# EE209_Sch_Team08.net
KiCad netlist of a schematic drawn in Altium Designer
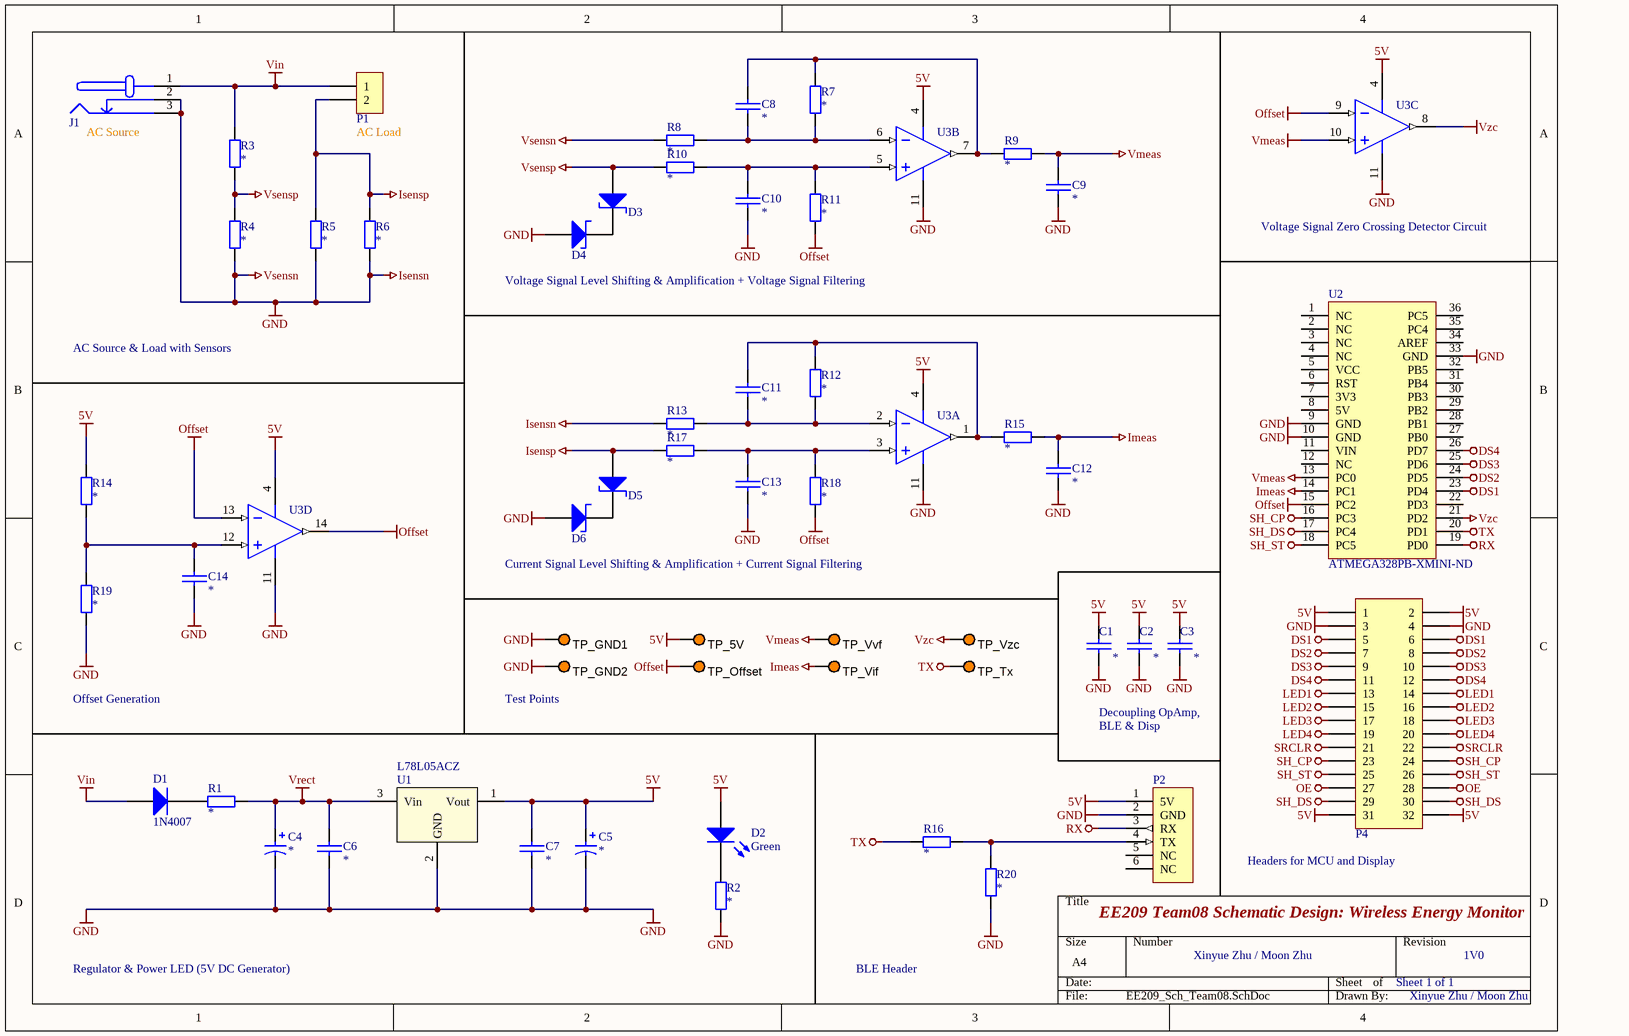
[diagram p0: EE209_Sch_Team08.SchDoc]

(export (version "E")
  (design (tool "Eeschema 10.0.6"))
  (components
    (comp (ref "C1")
      (value "*")
      (footprint "CCAP-5P0")
      (description "TH ceramic capacitor with 5mm pitch")
      (libsource (lib "EE209_Library") (part "CerCap_TH_5P0"))
    )
    (comp (ref "C2")
      (value "*")
      (footprint "CCAP-5P0")
      (description "TH ceramic capacitor with 5mm pitch")
      (libsource (lib "EE209_Library") (part "CerCap_TH_5P0"))
    )
    (comp (ref "C3")
      (value "*")
      (footprint "CCAP-5P0")
      (description "TH ceramic capacitor with 5mm pitch")
      (libsource (lib "EE209_Library") (part "CerCap_TH_5P0"))
    )
    (comp (ref "C4")
      (value "*")
      (footprint "CAP-RAD-2.5mm Pitch")
      (description "Electrolytic capacitor with radial package, 2mm pitch and 5.2mm diameter")
      (fields (field (name "PUBLISHER") "Altium Limited"))
      (libsource (lib "EE209_Library") (part "ElecCap_TH_2P0"))
    )
    (comp (ref "C5")
      (value "*")
      (footprint "CAP-RAD-2.5mm Pitch")
      (description "Electrolytic capacitor with radial package, 2mm pitch and 5.2mm diameter")
      (fields (field (name "PUBLISHER") "Altium Limited"))
      (libsource (lib "EE209_Library") (part "ElecCap_TH_2P0"))
    )
    (comp (ref "C6")
      (value "*")
      (footprint "CCAP-5P0")
      (description "TH ceramic capacitor with 5mm pitch")
      (libsource (lib "EE209_Library") (part "CerCap_TH_5P0"))
    )
    (comp (ref "C7")
      (value "*")
      (footprint "CCAP-5P0")
      (description "TH ceramic capacitor with 5mm pitch")
      (libsource (lib "EE209_Library") (part "CerCap_TH_5P0"))
    )
    (comp (ref "C8")
      (value "*")
      (footprint "CCAP-5P0")
      (description "TH ceramic capacitor with 5mm pitch")
      (libsource (lib "EE209_Library") (part "CerCap_TH_5P0"))
    )
    (comp (ref "C9")
      (value "*")
      (footprint "CCAP-5P0")
      (description "TH ceramic capacitor with 5mm pitch")
      (libsource (lib "EE209_Library") (part "CerCap_TH_5P0"))
    )
    (comp (ref "C10")
      (value "*")
      (footprint "CCAP-5P0")
      (description "TH ceramic capacitor with 5mm pitch")
      (libsource (lib "EE209_Library") (part "CerCap_TH_5P0"))
    )
    (comp (ref "C11")
      (value "*")
      (footprint "CCAP-5P0")
      (description "TH ceramic capacitor with 5mm pitch")
      (libsource (lib "EE209_Library") (part "CerCap_TH_5P0"))
    )
    (comp (ref "C12")
      (value "*")
      (footprint "CCAP-5P0")
      (description "TH ceramic capacitor with 5mm pitch")
      (libsource (lib "EE209_Library") (part "CerCap_TH_5P0"))
    )
    (comp (ref "C13")
      (value "*")
      (footprint "CCAP-5P0")
      (description "TH ceramic capacitor with 5mm pitch")
      (libsource (lib "EE209_Library") (part "CerCap_TH_5P0"))
    )
    (comp (ref "C14")
      (value "*")
      (footprint "CCAP-5P0")
      (description "TH ceramic capacitor with 5mm pitch")
      (libsource (lib "EE209_Library") (part "CerCap_TH_5P0"))
    )
    (comp (ref "D1")
      (value "1N4007")
      (footprint "1N4007-MFG")
      (description "1N4007 1000V standard axial diode")
      (libsource (lib "EE209_Library") (part "1N4007_TH_4AX0"))
    )
    (comp (ref "D2")
      (value "Green")
      (footprint "LED")
      (description "Typical throughole GaAs LED with 2.54mm pitch")
      (fields (field (name "MANUFACTURER") "Generic Components") (field (name "PUBLISHER") "Altium Limited"))
      (libsource (lib "EE209_Library") (part "LED_TH_2P54"))
    )
    (comp (ref "D3")
      (value "BZX79-CXVX")
      (footprint "AXIAL-Zener-0.4")
      (description "Axial zener diode BZX79 series")
      (fields
        (field (name "MANUFACTURER") "Nexperia USA Inc.")
        (field (name "MANUFACTURER PART NUMBER") "BZX79-C4V7,143")
      )
      (libsource (lib "EE209_Library") (part "Zener_TH_4AX0"))
    )
    (comp (ref "D4")
      (value "BZX79-CXVX")
      (footprint "AXIAL-Zener-0.4")
      (description "Axial zener diode BZX79 series")
      (fields
        (field (name "MANUFACTURER") "Nexperia USA Inc.")
        (field (name "MANUFACTURER PART NUMBER") "BZX79-C4V7,143")
      )
      (libsource (lib "EE209_Library") (part "Zener_TH_4AX0"))
    )
    (comp (ref "D5")
      (value "BZX79-CXVX")
      (footprint "AXIAL-Zener-0.4")
      (description "Axial zener diode BZX79 series")
      (fields
        (field (name "MANUFACTURER") "Nexperia USA Inc.")
        (field (name "MANUFACTURER PART NUMBER") "BZX79-C4V7,143")
      )
      (libsource (lib "EE209_Library") (part "Zener_TH_4AX0"))
    )
    (comp (ref "D6")
      (value "BZX79-CXVX")
      (footprint "AXIAL-Zener-0.4")
      (description "Axial zener diode BZX79 series")
      (fields
        (field (name "MANUFACTURER") "Nexperia USA Inc.")
        (field (name "MANUFACTURER PART NUMBER") "BZX79-C4V7,143")
      )
      (libsource (lib "EE209_Library") (part "Zener_TH_4AX0"))
    )
    (comp (ref "J1")
      (value "DC barrel jack")
      (footprint "AC-Socket")
      (description "DC barrel jack connection to AC source")
      (libsource (lib "EE209_Library") (part "AC_Input"))
    )
    (comp (ref "P1")
      (value "Dual Banana Plugs")
      (footprint "Dual Banana Plug")
      (description "Dual banana plugs connection to the AC load")
      (fields (field (name "PUBLISHER") "Altium Limited"))
      (libsource (lib "EE209_Library") (part "AC_Output"))
    )
    (comp (ref "P2")
      (value "BLE Module Header")
      (footprint "HM10_HDR1X6")
      (description "2.54mm pitch 6-pin header for BLE module")
      (fields (field (name "PUBLISHER") "Altium Limited"))
      (libsource (lib "EE209_Library") (part "BLEModule_TH"))
    )
    (comp (ref "P4")
      (value "Display")
      (footprint "Display")
      (description "16-Pin Header Connecting Display")
      (libsource (lib "EE209_Library") (part "Display"))
    )
    (comp (ref "R1")
      (value "*")
      (footprint "AXIAL-0.4")
      (description "Through hole resistor")
      (fields (field (name "PUBLISHER") "Altium Limited"))
      (libsource (lib "") (part "Res_TH_0AX4_1"))
    )
    (comp (ref "R2")
      (value "*")
      (footprint "AXIAL-0.4")
      (description "Through hole resistor")
      (fields (field (name "PUBLISHER") "Altium Limited"))
      (libsource (lib "") (part "Res_TH_0AX4_2"))
    )
    (comp (ref "R3")
      (value "*")
      (footprint "AXIAL-0.4")
      (description "Through hole resistor")
      (fields (field (name "PUBLISHER") "Altium Limited"))
      (libsource (lib "") (part "Res_TH_0AX4_2"))
    )
    (comp (ref "R4")
      (value "*")
      (footprint "AXIAL-0.4")
      (description "Through hole resistor")
      (fields (field (name "PUBLISHER") "Altium Limited"))
      (libsource (lib "") (part "Res_TH_0AX4_2"))
    )
    (comp (ref "R5")
      (value "*")
      (footprint "AXIAL-0.4")
      (description "Through hole resistor")
      (fields (field (name "PUBLISHER") "Altium Limited"))
      (libsource (lib "") (part "Res_TH_0AX4_2"))
    )
    (comp (ref "R6")
      (value "*")
      (footprint "AXIAL-0.4")
      (description "Through hole resistor")
      (fields (field (name "PUBLISHER") "Altium Limited"))
      (libsource (lib "") (part "Res_TH_0AX4_2"))
    )
    (comp (ref "R7")
      (value "*")
      (footprint "AXIAL-0.4")
      (description "Through hole resistor")
      (fields (field (name "PUBLISHER") "Altium Limited"))
      (libsource (lib "") (part "Res_TH_0AX4_2"))
    )
    (comp (ref "R8")
      (value "*")
      (footprint "AXIAL-0.4")
      (description "Through hole resistor")
      (fields (field (name "PUBLISHER") "Altium Limited"))
      (libsource (lib "EE209_Library") (part "Res_TH_0AX4"))
    )
    (comp (ref "R9")
      (value "*")
      (footprint "AXIAL-0.4")
      (description "Through hole resistor")
      (fields (field (name "PUBLISHER") "Altium Limited"))
      (libsource (lib "EE209_Library") (part "Res_TH_0AX4"))
    )
    (comp (ref "R10")
      (value "*")
      (footprint "AXIAL-0.4")
      (description "Through hole resistor")
      (fields (field (name "PUBLISHER") "Altium Limited"))
      (libsource (lib "EE209_Library") (part "Res_TH_0AX4"))
    )
    (comp (ref "R11")
      (value "*")
      (footprint "AXIAL-0.4")
      (description "Through hole resistor")
      (fields (field (name "PUBLISHER") "Altium Limited"))
      (libsource (lib "") (part "Res_TH_0AX4_2"))
    )
    (comp (ref "R12")
      (value "*")
      (footprint "AXIAL-0.4")
      (description "Through hole resistor")
      (fields (field (name "PUBLISHER") "Altium Limited"))
      (libsource (lib "") (part "Res_TH_0AX4_2"))
    )
    (comp (ref "R13")
      (value "*")
      (footprint "AXIAL-0.4")
      (description "Through hole resistor")
      (fields (field (name "PUBLISHER") "Altium Limited"))
      (libsource (lib "EE209_Library") (part "Res_TH_0AX4"))
    )
    (comp (ref "R14")
      (value "*")
      (footprint "AXIAL-0.4")
      (description "Through hole resistor")
      (fields (field (name "PUBLISHER") "Altium Limited"))
      (libsource (lib "") (part "Res_TH_0AX4_3"))
    )
    (comp (ref "R15")
      (value "*")
      (footprint "AXIAL-0.4")
      (description "Through hole resistor")
      (fields (field (name "PUBLISHER") "Altium Limited"))
      (libsource (lib "EE209_Library") (part "Res_TH_0AX4"))
    )
    (comp (ref "R16")
      (value "*")
      (footprint "AXIAL-0.4")
      (description "Through hole resistor")
      (fields (field (name "PUBLISHER") "Altium Limited"))
      (libsource (lib "") (part "Res_TH_0AX4_1"))
    )
    (comp (ref "R17")
      (value "*")
      (footprint "AXIAL-0.4")
      (description "Through hole resistor")
      (fields (field (name "PUBLISHER") "Altium Limited"))
      (libsource (lib "EE209_Library") (part "Res_TH_0AX4"))
    )
    (comp (ref "R18")
      (value "*")
      (footprint "AXIAL-0.4")
      (description "Through hole resistor")
      (fields (field (name "PUBLISHER") "Altium Limited"))
      (libsource (lib "") (part "Res_TH_0AX4_2"))
    )
    (comp (ref "R19")
      (value "*")
      (footprint "AXIAL-0.4")
      (description "Through hole resistor")
      (fields (field (name "PUBLISHER") "Altium Limited"))
      (libsource (lib "") (part "Res_TH_0AX4_2"))
    )
    (comp (ref "R20")
      (value "*")
      (footprint "AXIAL-0.4")
      (description "Through hole resistor")
      (fields (field (name "PUBLISHER") "Altium Limited"))
      (libsource (lib "") (part "Res_TH_0AX4_2"))
    )
    (comp (ref "TP_5V")
      (value "5003")
      (footprint "TP_TH")
      (description "Test Point, Orange, 1-Pin THD, RoHS")
      (libsource (lib "EE209_Library") (part "TestPoint"))
    )
    (comp (ref "TP_GND1")
      (value "5003")
      (footprint "TP_TH")
      (description "Test Point, Orange, 1-Pin THD, RoHS")
      (libsource (lib "EE209_Library") (part "TestPoint"))
    )
    (comp (ref "TP_GND2")
      (value "5003")
      (footprint "TP_TH")
      (description "Test Point, Orange, 1-Pin THD, RoHS")
      (libsource (lib "EE209_Library") (part "TestPoint"))
    )
    (comp (ref "TP_Offset")
      (value "5003")
      (footprint "TP_TH")
      (description "Test Point, Orange, 1-Pin THD, RoHS")
      (libsource (lib "EE209_Library") (part "TestPoint"))
    )
    (comp (ref "TP_Tx")
      (value "5003")
      (footprint "TP_TH")
      (description "Test Point, Orange, 1-Pin THD, RoHS")
      (libsource (lib "EE209_Library") (part "TestPoint"))
    )
    (comp (ref "TP_Vif")
      (value "5003")
      (footprint "TP_TH")
      (description "Test Point, Orange, 1-Pin THD, RoHS")
      (libsource (lib "EE209_Library") (part "TestPoint"))
    )
    (comp (ref "TP_Vvf")
      (value "5003")
      (footprint "TP_TH")
      (description "Test Point, Orange, 1-Pin THD, RoHS")
      (libsource (lib "EE209_Library") (part "TestPoint"))
    )
    (comp (ref "TP_Vzc")
      (value "5003")
      (footprint "TP_TH")
      (description "Test Point, Orange, 1-Pin THD, RoHS")
      (libsource (lib "EE209_Library") (part "TestPoint"))
    )
    (comp (ref "U1")
      (value "L78L05ACZ")
      (footprint "TO-92")
      (description "Voltage Regulator 5V")
      (fields
        (field (name "MANUFACTURER") "ON Semiconductor")
        (field (name "MANUFACTURER PART NUMBER") "LM78L05ACZX")
      )
      (libsource (lib "EE209_Library") (part "L78L05_TH_TO92"))
    )
    (comp (ref "U2")
      (value "ATmega328PB Xplained Mini Header")
      (footprint "ATmeg328P Xplained")
      (description "Dual 18-pin headers connecting to ATmega328PB Xplained Mini")
      (fields
        (field (name "MANUFACTURER") "Microchip Technology")
        (field (name "MANUFACTURER PART NUMBER") "ATMEGA328PB-XMINI")
        (field (name "SUPPLIER PART NUMBER 1") "ATMEGA328PB-XMINI-ND")
      )
      (libsource (lib "EE209_Library") (part "ATmega328PBXplained_TH"))
    )
    (comp (ref "U3")
      (value "LM324")
      (footprint "DIP-14")
      (description "IC OPAMP GP 14DIP")
      (fields
        (field (name "MANUFACTURER") "ON Semiconductor")
        (field (name "MANUFACTURER PART NUMBER") "LM324N")
      )
      (libsource (lib "EE209_Library") (part "LM324N_TH_DIP16"))
    )
  )
  (nets
    (net (code "1") (name "5V") (class "Default")
      (node (ref "C1") (pin "1") (pinfunction "1_1") (pintype "passive"))
      (node (ref "C2") (pin "1") (pinfunction "1_1") (pintype "passive"))
      (node (ref "C3") (pin "1") (pinfunction "1_1") (pintype "passive"))
      (node (ref "C5") (pin "1") (pinfunction "1_1") (pintype "passive"))
      (node (ref "C7") (pin "1") (pinfunction "1_1") (pintype "passive"))
      (node (ref "D2") (pin "1") (pinfunction "A_1") (pintype "passive"))
      (node (ref "P2") (pin "1") (pinfunction "5V_1") (pintype "passive"))
      (node (ref "P4") (pin "1") (pinfunction "1_1") (pintype "passive"))
      (node (ref "P4") (pin "2") (pinfunction "2_2") (pintype "passive"))
      (node (ref "P4") (pin "31") (pinfunction "31_31") (pintype "passive"))
      (node (ref "P4") (pin "32") (pinfunction "32_32") (pintype "passive"))
      (node (ref "R14") (pin "1") (pinfunction "1_1") (pintype "passive"))
      (node (ref "TP_5V") (pin "1") (pinfunction "1_1") (pintype "passive"))
      (node (ref "U1") (pin "1") (pinfunction "Vout_1") (pintype "passive"))
      (node (ref "U3") (pin "4") (pinfunction "VDD_4") (pintype "power_in"))
    )
    (net (code "2") (name "DS1") (class "Default")
      (node (ref "P4") (pin "5") (pinfunction "5_5") (pintype "passive"))
      (node (ref "P4") (pin "6") (pinfunction "6_6") (pintype "passive"))
      (node (ref "U2") (pin "23") (pinfunction "PD4_23") (pintype "passive"))
    )
    (net (code "3") (name "DS2") (class "Default")
      (node (ref "P4") (pin "7") (pinfunction "7_7") (pintype "passive"))
      (node (ref "P4") (pin "8") (pinfunction "8_8") (pintype "passive"))
      (node (ref "U2") (pin "24") (pinfunction "PD5_24") (pintype "passive"))
    )
    (net (code "4") (name "DS3") (class "Default")
      (node (ref "P4") (pin "10") (pinfunction "10_10") (pintype "passive"))
      (node (ref "P4") (pin "9") (pinfunction "9_9") (pintype "passive"))
      (node (ref "U2") (pin "25") (pinfunction "PD6_25") (pintype "passive"))
    )
    (net (code "5") (name "DS4") (class "Default")
      (node (ref "P4") (pin "11") (pinfunction "11_11") (pintype "passive"))
      (node (ref "P4") (pin "12") (pinfunction "12_12") (pintype "passive"))
      (node (ref "U2") (pin "26") (pinfunction "PD7_26") (pintype "passive"))
    )
    (net (code "6") (name "GND") (class "Default")
      (node (ref "C1") (pin "2") (pinfunction "2_2") (pintype "passive"))
      (node (ref "C10") (pin "2") (pinfunction "2_2") (pintype "passive"))
      (node (ref "C12") (pin "2") (pinfunction "2_2") (pintype "passive"))
      (node (ref "C13") (pin "2") (pinfunction "2_2") (pintype "passive"))
      (node (ref "C14") (pin "2") (pinfunction "2_2") (pintype "passive"))
      (node (ref "C2") (pin "2") (pinfunction "2_2") (pintype "passive"))
      (node (ref "C3") (pin "2") (pinfunction "2_2") (pintype "passive"))
      (node (ref "C4") (pin "2") (pinfunction "2_2") (pintype "passive"))
      (node (ref "C5") (pin "2") (pinfunction "2_2") (pintype "passive"))
      (node (ref "C6") (pin "2") (pinfunction "2_2") (pintype "passive"))
      (node (ref "C7") (pin "2") (pinfunction "2_2") (pintype "passive"))
      (node (ref "C9") (pin "2") (pinfunction "2_2") (pintype "passive"))
      (node (ref "D4") (pin "1") (pinfunction "A_1") (pintype "passive"))
      (node (ref "D6") (pin "1") (pinfunction "A_1") (pintype "passive"))
      (node (ref "J1") (pin "2") (pinfunction "GND_ALT_2") (pintype "power_in"))
      (node (ref "J1") (pin "3") (pinfunction "GND_3") (pintype "power_in"))
      (node (ref "P2") (pin "2") (pinfunction "GND_2") (pintype "passive"))
      (node (ref "P4") (pin "3") (pinfunction "3_3") (pintype "passive"))
      (node (ref "P4") (pin "4") (pinfunction "4_4") (pintype "passive"))
      (node (ref "R13") (pin "2") (pinfunction "2_2") (pintype "passive"))
      (node (ref "R19") (pin "1") (pinfunction "1_1") (pintype "passive"))
      (node (ref "R2") (pin "1") (pinfunction "1_1") (pintype "passive"))
      (node (ref "R20") (pin "1") (pinfunction "1_1") (pintype "passive"))
      (node (ref "R4") (pin "1") (pinfunction "1_1") (pintype "passive"))
      (node (ref "R5") (pin "1") (pinfunction "1_1") (pintype "passive"))
      (node (ref "R6") (pin "1") (pinfunction "1_1") (pintype "passive"))
      (node (ref "R8") (pin "2") (pinfunction "2_2") (pintype "passive"))
      (node (ref "TP_GND1") (pin "1") (pinfunction "1_1") (pintype "passive"))
      (node (ref "TP_GND2") (pin "1") (pinfunction "1_1") (pintype "passive"))
      (node (ref "U1") (pin "2") (pinfunction "GND_2") (pintype "passive"))
      (node (ref "U2") (pin "10") (pinfunction "GND_10") (pintype "power_in"))
      (node (ref "U2") (pin "33") (pinfunction "GND_33") (pintype "passive"))
      (node (ref "U2") (pin "9") (pinfunction "GND_9") (pintype "power_in"))
      (node (ref "U3") (pin "11") (pinfunction "VSS_11") (pintype "power_in"))
    )
    (net (code "7") (name "Imeas") (class "Default")
      (node (ref "C12") (pin "1") (pinfunction "1_1") (pintype "passive"))
      (node (ref "R15") (pin "1") (pinfunction "1_1") (pintype "passive"))
      (node (ref "TP_Vif") (pin "1") (pinfunction "1_1") (pintype "passive"))
      (node (ref "U2") (pin "14") (pinfunction "PC1_14") (pintype "passive"))
    )
    (net (code "8") (name "Isensp") (class "Default")
      (node (ref "D5") (pin "1") (pinfunction "A_1") (pintype "passive"))
      (node (ref "P1") (pin "2") (pinfunction "2_2") (pintype "passive"))
      (node (ref "R17") (pin "2") (pinfunction "2_2") (pintype "passive"))
      (node (ref "R5") (pin "2") (pinfunction "2_2") (pintype "passive"))
      (node (ref "R6") (pin "2") (pinfunction "2_2") (pintype "passive"))
    )
    (net (code "9") (name "LED1") (class "Default")
      (node (ref "P4") (pin "13") (pinfunction "13_13") (pintype "passive"))
      (node (ref "P4") (pin "14") (pinfunction "14_14") (pintype "passive"))
    )
    (net (code "10") (name "LED2") (class "Default")
      (node (ref "P4") (pin "15") (pinfunction "15_15") (pintype "passive"))
      (node (ref "P4") (pin "16") (pinfunction "16_16") (pintype "passive"))
    )
    (net (code "11") (name "LED3") (class "Default")
      (node (ref "P4") (pin "17") (pinfunction "17_17") (pintype "passive"))
      (node (ref "P4") (pin "18") (pinfunction "18_18") (pintype "passive"))
    )
    (net (code "12") (name "LED4") (class "Default")
      (node (ref "P4") (pin "19") (pinfunction "19_19") (pintype "passive"))
      (node (ref "P4") (pin "20") (pinfunction "20_20") (pintype "passive"))
    )
    (net (code "13") (name "Net-(D1-K)") (class "Default")
      (node (ref "D1") (pin "2") (pinfunction "K_2") (pintype "passive"))
      (node (ref "R1") (pin "1") (pinfunction "1_1") (pintype "passive"))
    )
    (net (code "14") (name "Net-(D2-K)") (class "Default")
      (node (ref "D2") (pin "2") (pinfunction "K_2") (pintype "passive"))
      (node (ref "R2") (pin "2") (pinfunction "2_2") (pintype "passive"))
    )
    (net (code "15") (name "Net-(D3-K)") (class "Default")
      (node (ref "D3") (pin "2") (pinfunction "K_2") (pintype "passive"))
      (node (ref "D4") (pin "2") (pinfunction "K_2") (pintype "passive"))
    )
    (net (code "16") (name "Net-(D5-K)") (class "Default")
      (node (ref "D5") (pin "2") (pinfunction "K_2") (pintype "passive"))
      (node (ref "D6") (pin "2") (pinfunction "K_2") (pintype "passive"))
    )
    (net (code "17") (name "Net-(P2-TX)") (class "Default")
      (node (ref "P2") (pin "4") (pinfunction "TX_4") (pintype "input"))
      (node (ref "R16") (pin "2") (pinfunction "2_2") (pintype "passive"))
      (node (ref "R20") (pin "2") (pinfunction "2_2") (pintype "passive"))
    )
    (net (code "18") (name "Net-(U3A-VINA+)") (class "Default")
      (node (ref "C13") (pin "1") (pinfunction "1_1") (pintype "passive"))
      (node (ref "R17") (pin "1") (pinfunction "1_1") (pintype "passive"))
      (node (ref "R18") (pin "2") (pinfunction "2_2") (pintype "passive"))
      (node (ref "U3") (pin "3") (pinfunction "VINA+_3") (pintype "input"))
    )
    (net (code "19") (name "Net-(U3A-VINA-)") (class "Default")
      (node (ref "C11") (pin "2") (pinfunction "2_2") (pintype "passive"))
      (node (ref "R12") (pin "1") (pinfunction "1_1") (pintype "passive"))
      (node (ref "R13") (pin "1") (pinfunction "1_1") (pintype "passive"))
      (node (ref "U3") (pin "2") (pinfunction "VINA-_2") (pintype "input"))
    )
    (net (code "20") (name "Net-(U3A-VOUTA)") (class "Default")
      (node (ref "C11") (pin "1") (pinfunction "1_1") (pintype "passive"))
      (node (ref "R12") (pin "2") (pinfunction "2_2") (pintype "passive"))
      (node (ref "R15") (pin "2") (pinfunction "2_2") (pintype "passive"))
      (node (ref "U3") (pin "1") (pinfunction "VOUTA_1") (pintype "output"))
    )
    (net (code "21") (name "Net-(U3B-VINB+)") (class "Default")
      (node (ref "C10") (pin "1") (pinfunction "1_1") (pintype "passive"))
      (node (ref "R10") (pin "1") (pinfunction "1_1") (pintype "passive"))
      (node (ref "R11") (pin "2") (pinfunction "2_2") (pintype "passive"))
      (node (ref "U3") (pin "5") (pinfunction "VINB+_5") (pintype "input"))
    )
    (net (code "22") (name "Net-(U3B-VINB-)") (class "Default")
      (node (ref "C8") (pin "2") (pinfunction "2_2") (pintype "passive"))
      (node (ref "R7") (pin "1") (pinfunction "1_1") (pintype "passive"))
      (node (ref "R8") (pin "1") (pinfunction "1_1") (pintype "passive"))
      (node (ref "U3") (pin "6") (pinfunction "VINB-_6") (pintype "input"))
    )
    (net (code "23") (name "Net-(U3B-VOUTB)") (class "Default")
      (node (ref "C8") (pin "1") (pinfunction "1_1") (pintype "passive"))
      (node (ref "R7") (pin "2") (pinfunction "2_2") (pintype "passive"))
      (node (ref "R9") (pin "2") (pinfunction "2_2") (pintype "passive"))
      (node (ref "U3") (pin "7") (pinfunction "VOUTB_7") (pintype "output"))
    )
    (net (code "24") (name "Net-(U3D-VIND+)") (class "Default")
      (node (ref "C14") (pin "1") (pinfunction "1_1") (pintype "passive"))
      (node (ref "R14") (pin "2") (pinfunction "2_2") (pintype "passive"))
      (node (ref "R19") (pin "2") (pinfunction "2_2") (pintype "passive"))
      (node (ref "U3") (pin "12") (pinfunction "VIND+_12") (pintype "input"))
    )
    (net (code "25") (name "OE") (class "Default")
      (node (ref "P4") (pin "27") (pinfunction "27_27") (pintype "passive"))
      (node (ref "P4") (pin "28") (pinfunction "28_28") (pintype "passive"))
    )
    (net (code "26") (name "Offset") (class "Default")
      (node (ref "R11") (pin "1") (pinfunction "1_1") (pintype "passive"))
      (node (ref "R18") (pin "1") (pinfunction "1_1") (pintype "passive"))
      (node (ref "TP_Offset") (pin "1") (pinfunction "1_1") (pintype "passive"))
      (node (ref "U2") (pin "15") (pinfunction "PC2_15") (pintype "passive"))
      (node (ref "U3") (pin "13") (pinfunction "VIND-_13") (pintype "input"))
      (node (ref "U3") (pin "14") (pinfunction "VOUTD_14") (pintype "output"))
      (node (ref "U3") (pin "9") (pinfunction "VINC-_9") (pintype "input"))
    )
    (net (code "27") (name "RX") (class "Default")
      (node (ref "P2") (pin "3") (pinfunction "RX_3") (pintype "output"))
      (node (ref "U2") (pin "19") (pinfunction "PD0_19") (pintype "passive"))
    )
    (net (code "28") (name "SH_CP") (class "Default")
      (node (ref "P4") (pin "23") (pinfunction "23_23") (pintype "passive"))
      (node (ref "P4") (pin "24") (pinfunction "24_24") (pintype "passive"))
      (node (ref "U2") (pin "16") (pinfunction "PC3_16") (pintype "passive"))
    )
    (net (code "29") (name "SH_DS") (class "Default")
      (node (ref "P4") (pin "29") (pinfunction "29_29") (pintype "passive"))
      (node (ref "P4") (pin "30") (pinfunction "30_30") (pintype "passive"))
      (node (ref "U2") (pin "17") (pinfunction "PC4_17") (pintype "passive"))
    )
    (net (code "30") (name "SH_ST") (class "Default")
      (node (ref "P4") (pin "25") (pinfunction "25_25") (pintype "passive"))
      (node (ref "P4") (pin "26") (pinfunction "26_26") (pintype "passive"))
      (node (ref "U2") (pin "18") (pinfunction "PC5_18") (pintype "passive"))
    )
    (net (code "31") (name "SRCLR") (class "Default")
      (node (ref "P4") (pin "21") (pinfunction "21_21") (pintype "passive"))
      (node (ref "P4") (pin "22") (pinfunction "22_22") (pintype "passive"))
    )
    (net (code "32") (name "TX") (class "Default")
      (node (ref "R16") (pin "1") (pinfunction "1_1") (pintype "passive"))
      (node (ref "TP_Tx") (pin "1") (pinfunction "1_1") (pintype "passive"))
      (node (ref "U2") (pin "20") (pinfunction "PD1_20") (pintype "passive"))
    )
    (net (code "33") (name "Vin") (class "Default")
      (node (ref "D1") (pin "1") (pinfunction "A_1") (pintype "passive"))
      (node (ref "J1") (pin "1") (pinfunction "VCC_1") (pintype "power_in"))
      (node (ref "P1") (pin "1") (pinfunction "1_1") (pintype "passive"))
      (node (ref "R3") (pin "2") (pinfunction "2_2") (pintype "passive"))
    )
    (net (code "34") (name "Vmeas") (class "Default")
      (node (ref "C9") (pin "1") (pinfunction "1_1") (pintype "passive"))
      (node (ref "R9") (pin "1") (pinfunction "1_1") (pintype "passive"))
      (node (ref "TP_Vvf") (pin "1") (pinfunction "1_1") (pintype "passive"))
      (node (ref "U2") (pin "13") (pinfunction "PC0_13") (pintype "passive"))
      (node (ref "U3") (pin "10") (pinfunction "VINC+_10") (pintype "input"))
    )
    (net (code "35") (name "Vrect") (class "Default")
      (node (ref "C4") (pin "1") (pinfunction "1_1") (pintype "passive"))
      (node (ref "C6") (pin "1") (pinfunction "1_1") (pintype "passive"))
      (node (ref "R1") (pin "2") (pinfunction "2_2") (pintype "passive"))
      (node (ref "U1") (pin "3") (pinfunction "Vin_3") (pintype "passive"))
    )
    (net (code "36") (name "Vsensp") (class "Default")
      (node (ref "D3") (pin "1") (pinfunction "A_1") (pintype "passive"))
      (node (ref "R10") (pin "2") (pinfunction "2_2") (pintype "passive"))
      (node (ref "R3") (pin "1") (pinfunction "1_1") (pintype "passive"))
      (node (ref "R4") (pin "2") (pinfunction "2_2") (pintype "passive"))
    )
    (net (code "37") (name "Vzc") (class "Default")
      (node (ref "TP_Vzc") (pin "1") (pinfunction "1_1") (pintype "passive"))
      (node (ref "U2") (pin "21") (pinfunction "PD2_21") (pintype "passive"))
      (node (ref "U3") (pin "8") (pinfunction "VOUTC_8") (pintype "output"))
    )
    (net (code "38") (name "unconnected-(P2-NC-Pad5)") (class "Default")
      (node (ref "P2") (pin "5") (pinfunction "NC_5") (pintype "passive"))
    )
    (net (code "39") (name "unconnected-(P2-NC-Pad6)") (class "Default")
      (node (ref "P2") (pin "6") (pinfunction "NC_6") (pintype "passive"))
    )
    (net (code "40") (name "unconnected-(U2-3V3-Pad7)") (class "Default")
      (node (ref "U2") (pin "7") (pinfunction "3V3_7") (pintype "passive"))
    )
    (net (code "41") (name "unconnected-(U2-5V-Pad8)") (class "Default")
      (node (ref "U2") (pin "8") (pinfunction "5V_8") (pintype "power_in"))
    )
    (net (code "42") (name "unconnected-(U2-AREF-Pad34)") (class "Default")
      (node (ref "U2") (pin "34") (pinfunction "AREF_34") (pintype "passive"))
    )
    (net (code "43") (name "unconnected-(U2-NC-Pad1)") (class "Default")
      (node (ref "U2") (pin "1") (pinfunction "NC_1") (pintype "passive"))
    )
    (net (code "44") (name "unconnected-(U2-NC-Pad2)") (class "Default")
      (node (ref "U2") (pin "2") (pinfunction "NC_2") (pintype "passive"))
    )
    (net (code "45") (name "unconnected-(U2-NC-Pad3)") (class "Default")
      (node (ref "U2") (pin "3") (pinfunction "NC_3") (pintype "passive"))
    )
    (net (code "46") (name "unconnected-(U2-NC-Pad4)") (class "Default")
      (node (ref "U2") (pin "4") (pinfunction "NC_4") (pintype "passive"))
    )
    (net (code "47") (name "unconnected-(U2-NC-Pad12)") (class "Default")
      (node (ref "U2") (pin "12") (pinfunction "NC_12") (pintype "passive"))
    )
    (net (code "48") (name "unconnected-(U2-PB0-Pad27)") (class "Default")
      (node (ref "U2") (pin "27") (pinfunction "PB0_27") (pintype "passive"))
    )
    (net (code "49") (name "unconnected-(U2-PB1-Pad28)") (class "Default")
      (node (ref "U2") (pin "28") (pinfunction "PB1_28") (pintype "passive"))
    )
    (net (code "50") (name "unconnected-(U2-PB2-Pad29)") (class "Default")
      (node (ref "U2") (pin "29") (pinfunction "PB2_29") (pintype "passive"))
    )
    (net (code "51") (name "unconnected-(U2-PB3-Pad30)") (class "Default")
      (node (ref "U2") (pin "30") (pinfunction "PB3_30") (pintype "passive"))
    )
    (net (code "52") (name "unconnected-(U2-PB4-Pad31)") (class "Default")
      (node (ref "U2") (pin "31") (pinfunction "PB4_31") (pintype "passive"))
    )
    (net (code "53") (name "unconnected-(U2-PB5-Pad32)") (class "Default")
      (node (ref "U2") (pin "32") (pinfunction "PB5_32") (pintype "passive"))
    )
    (net (code "54") (name "unconnected-(U2-PC4-Pad35)") (class "Default")
      (node (ref "U2") (pin "35") (pinfunction "PC4_35") (pintype "passive"))
    )
    (net (code "55") (name "unconnected-(U2-PC5-Pad36)") (class "Default")
      (node (ref "U2") (pin "36") (pinfunction "PC5_36") (pintype "passive"))
    )
    (net (code "56") (name "unconnected-(U2-PD3-Pad22)") (class "Default")
      (node (ref "U2") (pin "22") (pinfunction "PD3_22") (pintype "passive"))
    )
    (net (code "57") (name "unconnected-(U2-RST-Pad6)") (class "Default")
      (node (ref "U2") (pin "6") (pinfunction "RST_6") (pintype "passive"))
    )
    (net (code "58") (name "unconnected-(U2-VCC-Pad5)") (class "Default")
      (node (ref "U2") (pin "5") (pinfunction "VCC_5") (pintype "power_in"))
    )
    (net (code "59") (name "unconnected-(U2-VIN-Pad11)") (class "Default")
      (node (ref "U2") (pin "11") (pinfunction "VIN_11") (pintype "power_in"))
    )
  )
)
